# PX4FMUv2_4_6_5.net
KiCad netlist of a schematic drawn in Altium Designer
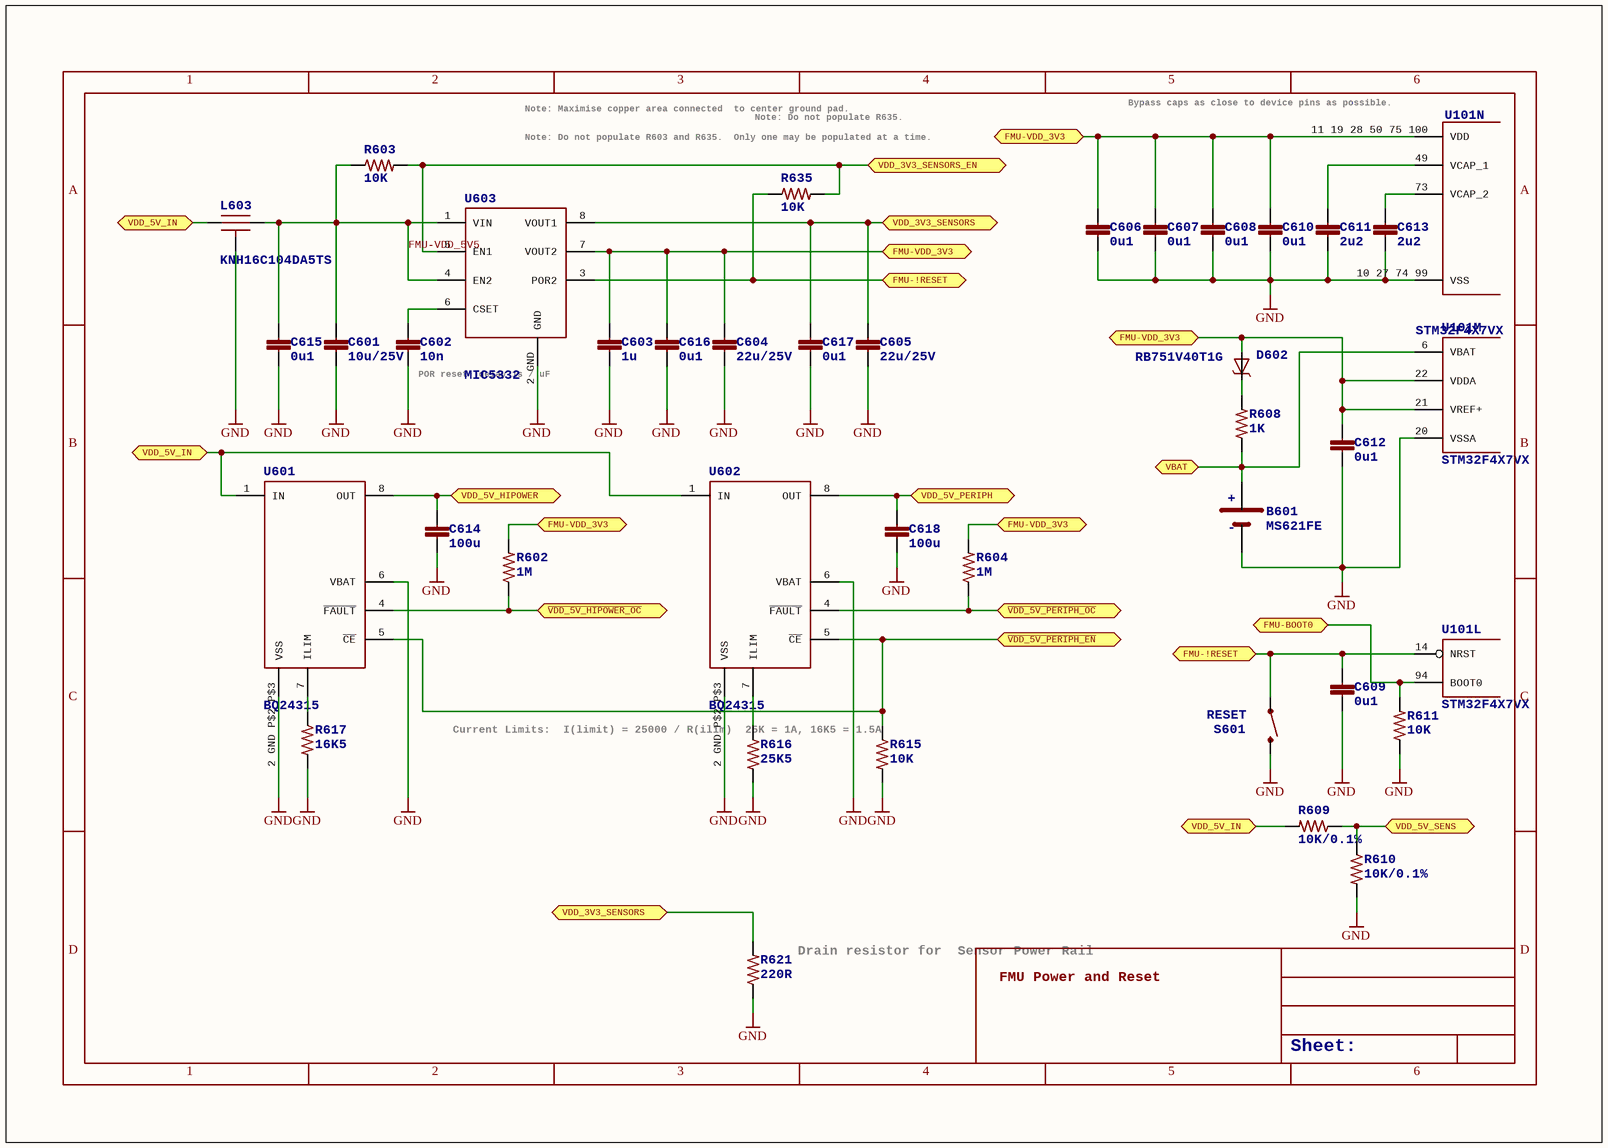
[diagram p0: PX4FMUv2.4.6_5.SchDoc]

(export (version "E")
  (design (tool "Eeschema 10.0.6"))
  (components
    (comp (ref "B601")
      (value "MS621FE")
      (footprint "MS621FE")
      (fields (field (name "PARTNO") "MS621FE-FL11E") (field (name "+") "+") (field (name "-") "-"))
      (libsource (lib "pixhawk2") (part "MS621FE"))
    )
    (comp (ref "C601")
      (value "10u/25V")
      (footprint "0805-CAP")
      (description "CapacitorStandard 0603 ceramic capacitor, and 0.1\" leaded capacitor.")
      (fields (field (name "PARTNO") "CL21A106KAYNNNE"))
      (libsource (lib "pixhawk2") (part "CAP0805"))
    )
    (comp (ref "C602")
      (value "10n")
      (footprint "0402-CAP")
      (description "CapacitorStandard 0603 ceramic capacitor, and 0.1\" leaded capacitor.")
      (fields (field (name "PARTNO") "CC0402KRX7R7BB103"))
      (libsource (lib "") (part "CAP0402_1"))
    )
    (comp (ref "C603")
      (value "1u")
      (footprint "0603-CAP")
      (description "CapacitorStandard 0603 ceramic capacitor, and 0.1\" leaded capacitor.")
      (fields (field (name "PARTNO") "CC0603ZRY5V7BB105"))
      (libsource (lib "pixhawk2") (part "CAP0603"))
    )
    (comp (ref "C604")
      (value "22u/25V")
      (footprint "0805-CAP")
      (description "CapacitorStandard 0603 ceramic capacitor, and 0.1\" leaded capacitor.")
      (fields (field (name "PARTNO") "CL21A226MAQNNNE"))
      (libsource (lib "pixhawk2") (part "CAP0805"))
    )
    (comp (ref "C605")
      (value "22u/25V")
      (footprint "0805-CAP")
      (description "CapacitorStandard 0603 ceramic capacitor, and 0.1\" leaded capacitor.")
      (fields (field (name "PARTNO") "CL21A226MAQNNNE"))
      (libsource (lib "pixhawk2") (part "CAP0805"))
    )
    (comp (ref "C606")
      (value "0u1")
      (footprint "0402-CAP")
      (description "CapacitorStandard 0603 ceramic capacitor, and 0.1\" leaded capacitor.")
      (fields (field (name "PARTNO") "CC0402ZRY5V7BB104"))
      (libsource (lib "pixhawk2") (part "CAP0402"))
    )
    (comp (ref "C607")
      (value "0u1")
      (footprint "0402-CAP")
      (description "CapacitorStandard 0603 ceramic capacitor, and 0.1\" leaded capacitor.")
      (fields (field (name "PARTNO") "CC0402ZRY5V7BB104"))
      (libsource (lib "pixhawk2") (part "CAP0402"))
    )
    (comp (ref "C608")
      (value "0u1")
      (footprint "0402-CAP")
      (description "CapacitorStandard 0603 ceramic capacitor, and 0.1\" leaded capacitor.")
      (fields (field (name "PARTNO") "CC0402ZRY5V7BB104"))
      (libsource (lib "pixhawk2") (part "CAP0402"))
    )
    (comp (ref "C609")
      (value "0u1")
      (footprint "0402-CAP")
      (description "CapacitorStandard 0603 ceramic capacitor, and 0.1\" leaded capacitor.")
      (fields (field (name "PARTNO") "CC0402ZRY5V7BB104"))
      (libsource (lib "") (part "CAP0402_2"))
    )
    (comp (ref "C610")
      (value "0u1")
      (footprint "0402-CAP")
      (description "CapacitorStandard 0603 ceramic capacitor, and 0.1\" leaded capacitor.")
      (fields (field (name "PARTNO") "CC0402ZRY5V7BB104"))
      (libsource (lib "pixhawk2") (part "CAP0402"))
    )
    (comp (ref "C611")
      (value "2u2")
      (footprint "0603-CAP")
      (description "CapacitorStandard 0603 ceramic capacitor, and 0.1\" leaded capacitor.")
      (fields (field (name "PARTNO") "C1608X6S1C225K080AC"))
      (libsource (lib "pixhawk2") (part "CAP0603"))
    )
    (comp (ref "C612")
      (value "0u1")
      (footprint "0402-CAP")
      (description "CapacitorStandard 0603 ceramic capacitor, and 0.1\" leaded capacitor.")
      (fields (field (name "PARTNO") "CC0402ZRY5V7BB104"))
      (libsource (lib "pixhawk2") (part "CAP0402"))
    )
    (comp (ref "C613")
      (value "2u2")
      (footprint "0603-CAP")
      (description "CapacitorStandard 0603 ceramic capacitor, and 0.1\" leaded capacitor.")
      (fields (field (name "PARTNO") "C1608X6S1C225K080AC"))
      (libsource (lib "pixhawk2") (part "CAP0603"))
    )
    (comp (ref "C614")
      (value "100u")
      (footprint "1206-CAP")
      (description "CapacitorStandard 0603 ceramic capacitor, and 0.1\" leaded capacitor.")
      (fields (field (name "PARTNO") "C3216X5R1A107M160AC"))
      (libsource (lib "pixhawk2") (part "CAP1206"))
    )
    (comp (ref "C615")
      (value "0u1")
      (footprint "0402-CAP")
      (description "CapacitorStandard 0603 ceramic capacitor, and 0.1\" leaded capacitor.")
      (fields (field (name "PARTNO") "CC0402ZRY5V7BB104"))
      (libsource (lib "pixhawk2") (part "CAP0402"))
    )
    (comp (ref "C616")
      (value "0u1")
      (footprint "0402-CAP")
      (description "CapacitorStandard 0603 ceramic capacitor, and 0.1\" leaded capacitor.")
      (fields (field (name "PARTNO") "CC0402ZRY5V7BB104"))
      (libsource (lib "pixhawk2") (part "CAP0402"))
    )
    (comp (ref "C617")
      (value "0u1")
      (footprint "0402-CAP")
      (description "CapacitorStandard 0603 ceramic capacitor, and 0.1\" leaded capacitor.")
      (fields (field (name "PARTNO") "CC0402ZRY5V7BB104"))
      (libsource (lib "pixhawk2") (part "CAP0402"))
    )
    (comp (ref "C618")
      (value "100u")
      (footprint "1206-CAP")
      (description "CapacitorStandard 0603 ceramic capacitor, and 0.1\" leaded capacitor.")
      (fields (field (name "PARTNO") "C3216X5R1A107M160AC"))
      (libsource (lib "pixhawk2") (part "CAP1206"))
    )
    (comp (ref "D602")
      (value "RB751V40T1G")
      (footprint "SOD323")
      (description "Schottky barrier diode in DO214AC, e.g. Fairchild SS14.")
      (libsource (lib "pixhawk2") (part "DIODE-SCHOTTKY_SOD323"))
    )
    (comp (ref "L603")
      (value "KNH16C104DA5TS")
      (footprint "KYOCERA-KNH16-DA")
      (description "Kyocera KNH16C104DA5TS EMI filter")
      (libsource (lib "pixhawk2") (part "KNH16C104DA5TS"))
    )
    (comp (ref "R602")
      (value "1M")
      (footprint "0402-RES")
      (fields (field (name "PARTNO") "RC0402FR-071ML"))
      (libsource (lib "pixhawk2") (part "RESISTOR0402-RES"))
    )
    (comp (ref "R603")
      (value "10K")
      (footprint "0402-RES")
      (fields (field (name "PARTNO") "RC0402FR-0710KL"))
      (libsource (lib "pixhawk2") (part "RESISTOR0402-RES"))
    )
    (comp (ref "R604")
      (value "1M")
      (footprint "0402-RES")
      (fields (field (name "PARTNO") "RC0402FR-071ML"))
      (libsource (lib "pixhawk2") (part "RESISTOR0402-RES"))
    )
    (comp (ref "R608")
      (value "1K")
      (footprint "0402-RES")
      (fields (field (name "PARTNO") "RC0402FR-071KL"))
      (libsource (lib "pixhawk2") (part "RESISTOR0402-RES"))
    )
    (comp (ref "R609")
      (value "10K/0.1%")
      (footprint "0402-RES")
      (fields (field (name "PARTNO") "ERA-2AEB103X"))
      (libsource (lib "pixhawk2") (part "RESISTOR0402-RES"))
    )
    (comp (ref "R610")
      (value "10K/0.1%")
      (footprint "0402-RES")
      (fields (field (name "PARTNO") "ERA-2AEB103X"))
      (libsource (lib "pixhawk2") (part "RESISTOR0402-RES"))
    )
    (comp (ref "R611")
      (value "10K")
      (footprint "0402-RES")
      (fields (field (name "PARTNO") "RC0402FR-0710KL"))
      (libsource (lib "pixhawk2") (part "RESISTOR0402-RES"))
    )
    (comp (ref "R615")
      (value "10K")
      (footprint "0402-RES")
      (fields (field (name "PARTNO") "RC0402FR-0710KL"))
      (libsource (lib "pixhawk2") (part "RESISTOR0402-RES"))
    )
    (comp (ref "R616")
      (value "25K5")
      (footprint "0402-RES")
      (fields (field (name "PARTNO") "RMCF0402FT25K5"))
      (libsource (lib "pixhawk2") (part "RESISTOR0402-RES"))
    )
    (comp (ref "R617")
      (value "16K5")
      (footprint "0402-RES")
      (fields (field (name "PARTNO") "RMCF0402FT16K5"))
      (libsource (lib "pixhawk2") (part "RESISTOR0402-RES"))
    )
    (comp (ref "R621")
      (value "220R")
      (footprint "0603-RES")
      (fields (field (name "PARTNO") "RC1608J100CS"))
      (libsource (lib "pixhawk2") (part "RESISTOR0603-RES"))
    )
    (comp (ref "R635")
      (value "10K")
      (footprint "0402-RES")
      (fields (field (name "PARTNO") "RC0402FR-0710KL"))
      (libsource (lib "pixhawk2") (part "RESISTOR0402-RES"))
    )
    (comp (ref "S601")
      (value "RESET")
      (footprint "EVQP7J01K")
      (libsource (lib "pixhawk2") (part "SWITCH-MOMENTARY-2"))
    )
    (comp (ref "U101")
      (value "STM32F4X7VX")
      (footprint "TQFP100")
      (fields (field (name "PARTNO") "STM32F427VI"))
      (libsource (lib "pixhawk2") (part "STM32F4X7VX"))
    )
    (comp (ref "U601")
      (value "BQ24315")
      (footprint "QFN8-DSG")
      (fields (field (name "PARTNO") "BQ24315DSGR"))
      (libsource (lib "pixhawk2") (part "BQ24315"))
    )
    (comp (ref "U602")
      (value "BQ24315")
      (footprint "QFN8-DSG")
      (fields (field (name "PARTNO") "BQ24315DSGR"))
      (libsource (lib "pixhawk2") (part "BQ24315"))
    )
    (comp (ref "U603")
      (value "MIC5332")
      (footprint "MLF-8-EPAD")
      (fields (field (name "PARTNO") "MIC5332-SSYMT"))
      (libsource (lib "pixhawk2") (part "MIC5332"))
    )
  )
  (nets
    (net (code "1") (name "/FMU-!RESET") (class "Default")
      (node (ref "C609") (pin "P$2") (pinfunction "2_P$2") (pintype "passive"))
      (node (ref "R635") (pin "P$1") (pinfunction "1_P$1") (pintype "passive"))
      (node (ref "S601") (pin "A1") (pinfunction "1_A1") (pintype "passive"))
      (node (ref "U101") (pin "14") (pinfunction "NRST_14") (pintype "passive"))
      (node (ref "U603") (pin "3") (pinfunction "POR2_3") (pintype "passive"))
    )
    (net (code "2") (name "/FMU-BOOT0") (class "Default")
      (node (ref "R611") (pin "P$2") (pinfunction "2_P$2") (pintype "passive"))
      (node (ref "U101") (pin "94") (pinfunction "BOOT0_94") (pintype "passive"))
    )
    (net (code "3") (name "/FMU-VDD_3V3") (class "Default")
      (node (ref "C603") (pin "P$1") (pinfunction "1_P$1") (pintype "passive"))
      (node (ref "C604") (pin "P$1") (pinfunction "1_P$1") (pintype "passive"))
      (node (ref "C606") (pin "P$1") (pinfunction "1_P$1") (pintype "passive"))
      (node (ref "C607") (pin "P$1") (pinfunction "1_P$1") (pintype "passive"))
      (node (ref "C608") (pin "P$1") (pinfunction "1_P$1") (pintype "passive"))
      (node (ref "C610") (pin "P$1") (pinfunction "1_P$1") (pintype "passive"))
      (node (ref "C612") (pin "P$1") (pinfunction "1_P$1") (pintype "passive"))
      (node (ref "C616") (pin "P$1") (pinfunction "1_P$1") (pintype "passive"))
      (node (ref "D602") (pin "A") (pinfunction "A_A") (pintype "passive"))
      (node (ref "R602") (pin "P$2") (pinfunction "2_P$2") (pintype "passive"))
      (node (ref "R604") (pin "P$2") (pinfunction "2_P$2") (pintype "passive"))
      (node (ref "U101") (pin "11_19_28_50_75_100") (pinfunction "VDD_11_19_28_50_75_100") (pintype "power_in"))
      (node (ref "U101") (pin "21") (pinfunction "VREF+_21") (pintype "passive"))
      (node (ref "U101") (pin "22") (pinfunction "VDDA_22") (pintype "power_in"))
      (node (ref "U603") (pin "7") (pinfunction "VOUT2_7") (pintype "passive"))
    )
    (net (code "4") (name "/FMU-VDD_5V5") (class "Default")
      (node (ref "C601") (pin "P$1") (pinfunction "1_P$1") (pintype "passive"))
      (node (ref "C615") (pin "P$1") (pinfunction "1_P$1") (pintype "passive"))
      (node (ref "L603") (pin "P$2") (pinfunction "P$2_P$2") (pintype "passive"))
      (node (ref "R603") (pin "P$1") (pinfunction "1_P$1") (pintype "passive"))
      (node (ref "U603") (pin "1") (pinfunction "VIN_1") (pintype "passive"))
      (node (ref "U603") (pin "4") (pinfunction "EN2_4") (pintype "passive"))
    )
    (net (code "5") (name "/VBAT") (class "Default")
      (node (ref "B601") (pin "1") (pinfunction "POS_1") (pintype "passive"))
      (node (ref "R608") (pin "P$1") (pinfunction "1_P$1") (pintype "passive"))
      (node (ref "U101") (pin "6") (pinfunction "VBAT_6") (pintype "power_in"))
    )
    (net (code "6") (name "/VDD_3V3_SENSORS") (class "Default")
      (node (ref "C605") (pin "P$1") (pinfunction "1_P$1") (pintype "passive"))
      (node (ref "C617") (pin "P$1") (pinfunction "1_P$1") (pintype "passive"))
      (node (ref "R621") (pin "2") (pinfunction "2_2") (pintype "passive"))
      (node (ref "U603") (pin "8") (pinfunction "VOUT1_8") (pintype "passive"))
    )
    (net (code "7") (name "/VDD_3V3_SENSORS_EN") (class "Default")
      (node (ref "R603") (pin "P$2") (pinfunction "2_P$2") (pintype "passive"))
      (node (ref "R635") (pin "P$2") (pinfunction "2_P$2") (pintype "passive"))
      (node (ref "U603") (pin "5") (pinfunction "EN1_5") (pintype "passive"))
    )
    (net (code "8") (name "/VDD_5V_HIPOWER") (class "Default")
      (node (ref "C614") (pin "P$1") (pinfunction "1_P$1") (pintype "passive"))
      (node (ref "U601") (pin "8") (pinfunction "OUT_8") (pintype "passive"))
    )
    (net (code "9") (name "/VDD_5V_IN") (class "Default")
      (node (ref "L603") (pin "P$1") (pinfunction "P$1_P$1") (pintype "passive"))
      (node (ref "R609") (pin "P$2") (pinfunction "2_P$2") (pintype "passive"))
      (node (ref "U601") (pin "1") (pinfunction "IN_1") (pintype "passive"))
      (node (ref "U602") (pin "1") (pinfunction "IN_1") (pintype "passive"))
    )
    (net (code "10") (name "/VDD_5V_PERIPH") (class "Default")
      (node (ref "C618") (pin "P$1") (pinfunction "1_P$1") (pintype "passive"))
      (node (ref "U602") (pin "8") (pinfunction "OUT_8") (pintype "passive"))
    )
    (net (code "11") (name "/VDD_5V_SENS") (class "Default")
      (node (ref "R609") (pin "P$1") (pinfunction "1_P$1") (pintype "passive"))
      (node (ref "R610") (pin "P$1") (pinfunction "1_P$1") (pintype "passive"))
    )
    (net (code "12") (name "/~{VDD_5V_HIPOWER_OC}") (class "Default")
      (node (ref "R602") (pin "P$1") (pinfunction "1_P$1") (pintype "passive"))
      (node (ref "U601") (pin "4") (pinfunction "~{FAULT}_4") (pintype "passive"))
    )
    (net (code "13") (name "/~{VDD_5V_PERIPH_EN}") (class "Default")
      (node (ref "R615") (pin "P$1") (pinfunction "1_P$1") (pintype "passive"))
      (node (ref "U601") (pin "5") (pinfunction "~{CE}_5") (pintype "passive"))
      (node (ref "U602") (pin "5") (pinfunction "~{CE}_5") (pintype "passive"))
    )
    (net (code "14") (name "/~{VDD_5V_PERIPH_OC}") (class "Default")
      (node (ref "R604") (pin "P$1") (pinfunction "1_P$1") (pintype "passive"))
      (node (ref "U602") (pin "4") (pinfunction "~{FAULT}_4") (pintype "passive"))
    )
    (net (code "15") (name "GND") (class "Default")
      (node (ref "B601") (pin "2") (pinfunction "NEG_2") (pintype "passive"))
      (node (ref "C601") (pin "P$2") (pinfunction "2_P$2") (pintype "passive"))
      (node (ref "C602") (pin "P$1") (pinfunction "1_P$1") (pintype "passive"))
      (node (ref "C603") (pin "P$2") (pinfunction "2_P$2") (pintype "passive"))
      (node (ref "C604") (pin "P$2") (pinfunction "2_P$2") (pintype "passive"))
      (node (ref "C605") (pin "P$2") (pinfunction "2_P$2") (pintype "passive"))
      (node (ref "C606") (pin "P$2") (pinfunction "2_P$2") (pintype "passive"))
      (node (ref "C607") (pin "P$2") (pinfunction "2_P$2") (pintype "passive"))
      (node (ref "C608") (pin "P$2") (pinfunction "2_P$2") (pintype "passive"))
      (node (ref "C609") (pin "P$1") (pinfunction "1_P$1") (pintype "passive"))
      (node (ref "C610") (pin "P$2") (pinfunction "2_P$2") (pintype "passive"))
      (node (ref "C611") (pin "P$2") (pinfunction "2_P$2") (pintype "passive"))
      (node (ref "C612") (pin "P$2") (pinfunction "2_P$2") (pintype "passive"))
      (node (ref "C613") (pin "P$2") (pinfunction "2_P$2") (pintype "passive"))
      (node (ref "C614") (pin "P$2") (pinfunction "2_P$2") (pintype "passive"))
      (node (ref "C615") (pin "P$2") (pinfunction "2_P$2") (pintype "passive"))
      (node (ref "C616") (pin "P$2") (pinfunction "2_P$2") (pintype "passive"))
      (node (ref "C617") (pin "P$2") (pinfunction "2_P$2") (pintype "passive"))
      (node (ref "C618") (pin "P$2") (pinfunction "2_P$2") (pintype "passive"))
      (node (ref "L603") (pin "P$3_P$4_P$5") (pinfunction "P$3_P$3_P$4_P$5") (pintype "passive"))
      (node (ref "R610") (pin "P$2") (pinfunction "2_P$2") (pintype "passive"))
      (node (ref "R611") (pin "P$1") (pinfunction "1_P$1") (pintype "passive"))
      (node (ref "R615") (pin "P$2") (pinfunction "2_P$2") (pintype "passive"))
      (node (ref "R616") (pin "P$2") (pinfunction "2_P$2") (pintype "passive"))
      (node (ref "R617") (pin "P$2") (pinfunction "2_P$2") (pintype "passive"))
      (node (ref "R621") (pin "1") (pinfunction "1_1") (pintype "passive"))
      (node (ref "S601") (pin "B3") (pinfunction "2_B3") (pintype "passive"))
      (node (ref "U101") (pin "10_27_74_99") (pinfunction "VSS_10_27_74_99") (pintype "power_in"))
      (node (ref "U101") (pin "20") (pinfunction "VSSA_20") (pintype "power_in"))
      (node (ref "U601") (pin "2_GND_P$2_P$3") (pinfunction "VSS_2_GND_P$2_P$3") (pintype "passive"))
      (node (ref "U601") (pin "6") (pinfunction "VBAT_6") (pintype "passive"))
      (node (ref "U602") (pin "2_GND_P$2_P$3") (pinfunction "VSS_2_GND_P$2_P$3") (pintype "passive"))
      (node (ref "U602") (pin "6") (pinfunction "VBAT_6") (pintype "passive"))
      (node (ref "U603") (pin "2_GND") (pinfunction "GND_2_GND") (pintype "passive"))
    )
    (net (code "16") (name "Net-(C602-2)") (class "Default")
      (node (ref "C602") (pin "P$2") (pinfunction "2_P$2") (pintype "passive"))
      (node (ref "U603") (pin "6") (pinfunction "CSET_6") (pintype "passive"))
    )
    (net (code "17") (name "Net-(C611-1)") (class "Default")
      (node (ref "C611") (pin "P$1") (pinfunction "1_P$1") (pintype "passive"))
      (node (ref "U101") (pin "49") (pinfunction "VCAP_1_49") (pintype "power_in"))
    )
    (net (code "18") (name "Net-(C613-1)") (class "Default")
      (node (ref "C613") (pin "P$1") (pinfunction "1_P$1") (pintype "passive"))
      (node (ref "U101") (pin "73") (pinfunction "VCAP_2_73") (pintype "power_in"))
    )
    (net (code "19") (name "Net-(R608-2)") (class "Default")
      (node (ref "D602") (pin "C") (pinfunction "C_C") (pintype "passive"))
      (node (ref "R608") (pin "P$2") (pinfunction "2_P$2") (pintype "passive"))
    )
    (net (code "20") (name "Net-(R616-1)") (class "Default")
      (node (ref "R616") (pin "P$1") (pinfunction "1_P$1") (pintype "passive"))
      (node (ref "U602") (pin "7") (pinfunction "ILIM_7") (pintype "passive"))
    )
    (net (code "21") (name "Net-(R617-1)") (class "Default")
      (node (ref "R617") (pin "P$1") (pinfunction "1_P$1") (pintype "passive"))
      (node (ref "U601") (pin "7") (pinfunction "ILIM_7") (pintype "passive"))
    )
  )
)
